# Headers.net
KiCad netlist of a schematic drawn in Altium Designer
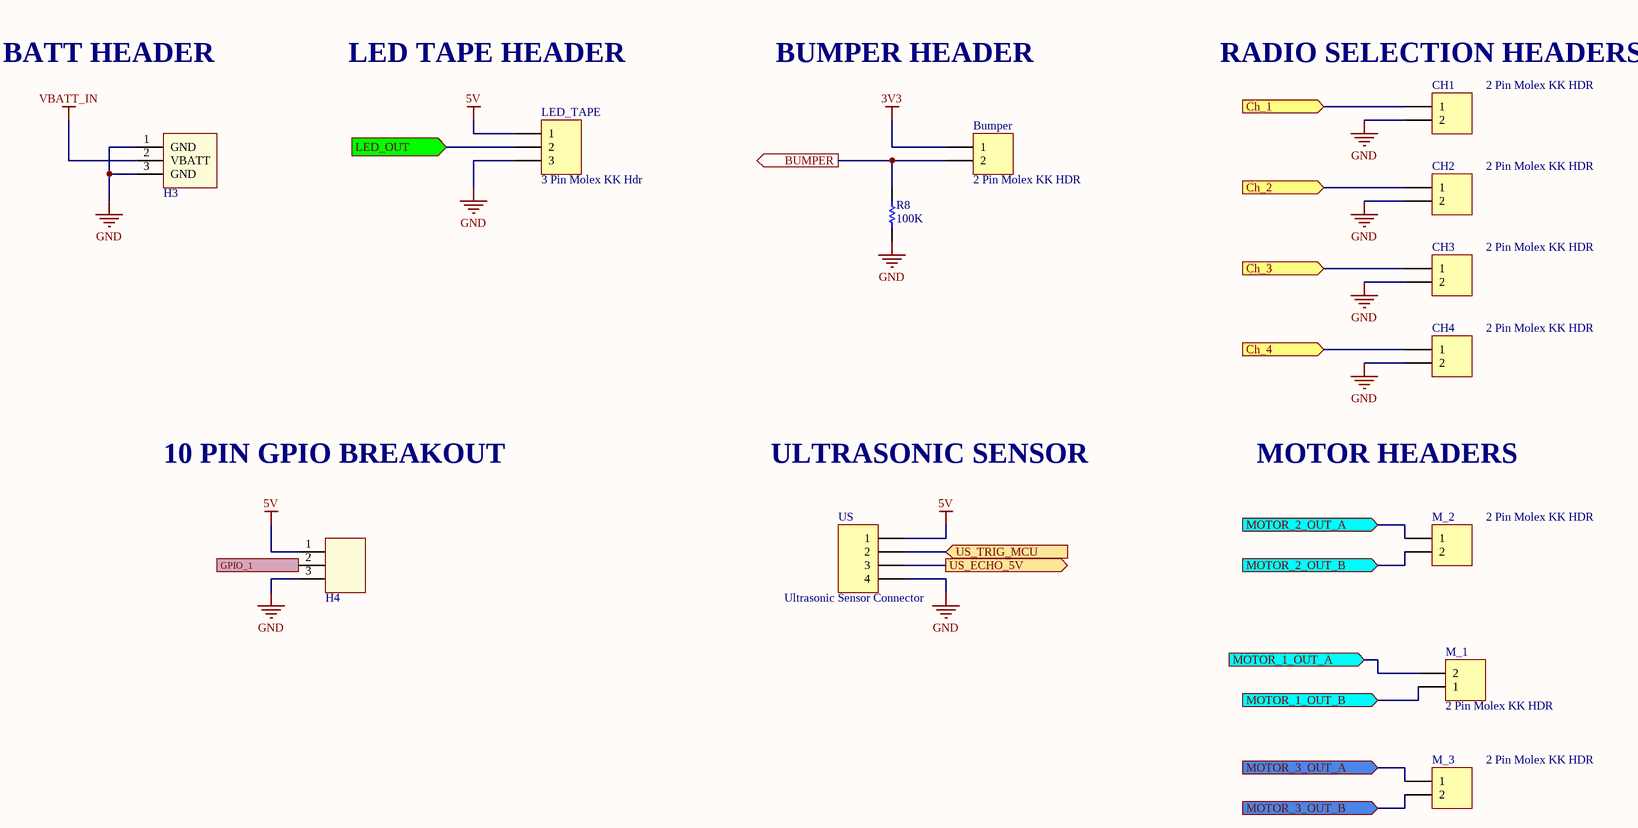
[diagram p0: Headers.SchDoc]

(export (version "E")
  (design (tool "Eeschema 10.0.6"))
  (components
    (comp (ref "Bumper")
      (value "2 Pin Molex KK HDR")
      (footprint "MOLEX_KK_2_HDR")
      (description "CONN HEADER 2POS 2.54mm VERT_Thru Hole")
      (libsource (lib "ECE AD19Components_19V1") (part "JA_MOLEX_KK_2POS"))
    )
    (comp (ref "CH1")
      (value "2 Pin Molex KK HDR")
      (footprint "MOLEX_KK_2_HDR")
      (description "CONN HEADER 2POS 2.54mm VERT_Thru Hole")
      (libsource (lib "ECE AD19Components_19V1") (part "JA_MOLEX_KK_2POS"))
    )
    (comp (ref "CH2")
      (value "2 Pin Molex KK HDR")
      (footprint "MOLEX_KK_2_HDR")
      (description "CONN HEADER 2POS 2.54mm VERT_Thru Hole")
      (libsource (lib "ECE AD19Components_19V1") (part "JA_MOLEX_KK_2POS"))
    )
    (comp (ref "CH3")
      (value "2 Pin Molex KK HDR")
      (footprint "MOLEX_KK_2_HDR")
      (description "CONN HEADER 2POS 2.54mm VERT_Thru Hole")
      (libsource (lib "ECE AD19Components_19V1") (part "JA_MOLEX_KK_2POS"))
    )
    (comp (ref "CH4")
      (value "2 Pin Molex KK HDR")
      (footprint "MOLEX_KK_2_HDR")
      (description "CONN HEADER 2POS 2.54mm VERT_Thru Hole")
      (libsource (lib "ECE AD19Components_19V1") (part "JA_MOLEX_KK_2POS"))
    )
    (comp (ref "H3")
      (value "Battery_HEADER_3pin")
      (footprint "BATT_HEADER_3POS")
      (description "3Pin Header 2.54mm spacing")
      (libsource (lib "ENCE461AD19_19V2") (part "Battery_HEADER_3pin"))
    )
    (comp (ref "H4")
      (value "HEADER_3")
      (footprint "HEADER_3POS")
      (description "3Pin Header 2.54mm spacing")
      (libsource (lib "ENCE461AD19_19V2") (part "HEADER_3"))
    )
    (comp (ref "LED_TAPE")
      (value "3 Pin Molex KK Hdr")
      (footprint "MOLEX_KK_3_HDR")
      (description "CONN HEADER 3POS 2.54mm VERT_Thru Hole")
      (fields (field (name "MANUFACTURER") "Molex"))
      (libsource (lib "ECE AD19Components_19V1") (part "JA_MOLEX_KK_3POS"))
    )
    (comp (ref "M_1")
      (value "2 Pin Molex KK HDR")
      (footprint "MOLEX_KK_2_HDR")
      (description "CONN HEADER 2POS 2.54mm VERT_Thru Hole")
      (libsource (lib "") (part "JA_MOLEX_KK_2POS_1"))
    )
    (comp (ref "M_2")
      (value "2 Pin Molex KK HDR")
      (footprint "MOLEX_KK_2_HDR")
      (description "CONN HEADER 2POS 2.54mm VERT_Thru Hole")
      (libsource (lib "ECE AD19Components_19V1") (part "JA_MOLEX_KK_2POS"))
    )
    (comp (ref "M_3")
      (value "2 Pin Molex KK HDR")
      (footprint "MOLEX_KK_2_HDR")
      (description "CONN HEADER 2POS 2.54mm VERT_Thru Hole")
      (libsource (lib "ECE AD19Components_19V1") (part "JA_MOLEX_KK_2POS"))
    )
    (comp (ref "R8")
      (value "100K")
      (footprint "RESC1608L")
      (description "RES 100K OHM 1/10W 5% 0603 SMD")
      (libsource (lib "ECE AD19Components_19V1") (part "RS_100K"))
    )
    (comp (ref "US")
      (value "Ultrasonic Sensor Connector")
      (footprint "MOLEX_KK_4_HDR")
      (description "CONN HEADER 4POS 2.54mm VERT_Thru Hole")
      (fields (field (name "MANUFACTURER") "Molex"))
      (libsource (lib "ECE AD19Components_19V1") (part "JA_MOLEX_KK_4POS"))
    )
  )
  (nets
    (net (code "2") (name "/BUMPER") (class "Default")
      (node (ref "Bumper") (pin "2") (pinfunction "2_2") (pintype "passive"))
      (node (ref "R8") (pin "2") (pinfunction "2_2") (pintype "passive"))
    )
    (net (code "3") (name "/Ch_1") (class "Default")
      (node (ref "CH1") (pin "1") (pinfunction "1_1") (pintype "passive"))
    )
    (net (code "4") (name "/Ch_2") (class "Default")
      (node (ref "CH2") (pin "1") (pinfunction "1_1") (pintype "passive"))
    )
    (net (code "5") (name "/Ch_3") (class "Default")
      (node (ref "CH3") (pin "1") (pinfunction "1_1") (pintype "passive"))
    )
    (net (code "6") (name "/Ch_4") (class "Default")
      (node (ref "CH4") (pin "1") (pinfunction "1_1") (pintype "passive"))
    )
    (net (code "7") (name "/GPIO_1") (class "Default") (node (ref "H4") (pin "2") (pintype "passive")))
    (net (code "8") (name "/LED_OUT") (class "Default")
      (node (ref "LED_TAPE") (pin "2") (pinfunction "2_2") (pintype "passive"))
    )
    (net (code "9") (name "/MOTOR_1_OUT_A") (class "Default")
      (node (ref "M_1") (pin "2") (pinfunction "2_2") (pintype "passive"))
    )
    (net (code "10") (name "/MOTOR_1_OUT_B") (class "Default")
      (node (ref "M_1") (pin "1") (pinfunction "1_1") (pintype "passive"))
    )
    (net (code "11") (name "/MOTOR_2_OUT_A") (class "Default")
      (node (ref "M_2") (pin "1") (pinfunction "1_1") (pintype "passive"))
    )
    (net (code "12") (name "/MOTOR_2_OUT_B") (class "Default")
      (node (ref "M_2") (pin "2") (pinfunction "2_2") (pintype "passive"))
    )
    (net (code "13") (name "/MOTOR_3_OUT_A") (class "Default")
      (node (ref "M_3") (pin "1") (pinfunction "1_1") (pintype "passive"))
    )
    (net (code "14") (name "/MOTOR_3_OUT_B") (class "Default")
      (node (ref "M_3") (pin "2") (pinfunction "2_2") (pintype "passive"))
    )
    (net (code "15") (name "/US_ECHO_5V") (class "Default")
      (node (ref "US") (pin "3") (pinfunction "3_3") (pintype "passive"))
    )
    (net (code "16") (name "/US_TRIG_MCU") (class "Default")
      (node (ref "US") (pin "2") (pinfunction "2_2") (pintype "passive"))
    )
    (net (code "17") (name "3V3") (class "Default")
      (node (ref "Bumper") (pin "1") (pinfunction "1_1") (pintype "passive"))
    )
    (net (code "18") (name "5V") (class "Default")
      (node (ref "H4") (pin "1") (pintype "passive"))
      (node (ref "LED_TAPE") (pin "1") (pinfunction "1_1") (pintype "passive"))
      (node (ref "US") (pin "1") (pinfunction "1_1") (pintype "passive"))
    )
    (net (code "19") (name "GND") (class "Default")
      (node (ref "CH1") (pin "2") (pinfunction "2_2") (pintype "passive"))
      (node (ref "CH2") (pin "2") (pinfunction "2_2") (pintype "passive"))
      (node (ref "CH3") (pin "2") (pinfunction "2_2") (pintype "passive"))
      (node (ref "CH4") (pin "2") (pinfunction "2_2") (pintype "passive"))
      (node (ref "H3") (pin "1") (pinfunction "GND_1") (pintype "passive"))
      (node (ref "H3") (pin "3") (pinfunction "GND_3") (pintype "passive"))
      (node (ref "H4") (pin "3") (pintype "passive"))
      (node (ref "LED_TAPE") (pin "3") (pinfunction "3_3") (pintype "passive"))
      (node (ref "R8") (pin "1") (pinfunction "1_1") (pintype "passive"))
      (node (ref "US") (pin "4") (pinfunction "4_4") (pintype "passive"))
    )
    (net (code "20") (name "VBATT_IN") (class "Default")
      (node (ref "H3") (pin "2") (pinfunction "VBATT_2") (pintype "passive"))
    )
  )
)
